# Flash.net
KiCad netlist of a schematic drawn in Altium Designer
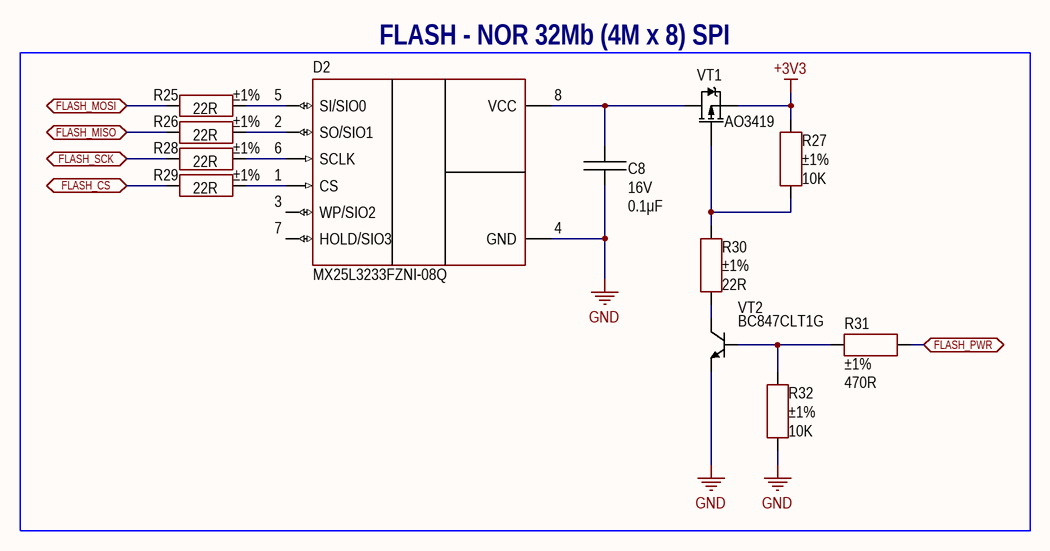
[diagram p0: Flash.SchDoc]

(export (version "E")
  (design (tool "Eeschema 10.0.6"))
  (components
    (comp (ref "C8")
      (value "0.1μF")
      (footprint "CAP: 0402")
      (description "±10% 16V Ceramic Capacitor X7R 0402 (1005 Metric)")
      (fields
        (field (name "MANUFACTURER") "Yageo")
        (field (name "PARTNUMBER") "CC0402KRX7R7BB104")
        (field (name "VOLTAGE") "16V")
      )
      (libsource (lib "capacitor") (part "Ceramic_0402"))
    )
    (comp (ref "D2")
      (value "~")
      (footprint "8-SOIC")
      (description "FLASH - NOR Memory IC 32Mb (8M x 4) SPI - Quad I/O 133 MHz 8-SOP")
      (fields
        (field (name "MANUFACTURER") "Macronix")
        (field (name "VALUEMANUFACTURERPARTNUMBER") "IC memory, FLASH, 32Mb (8M x 4), 133 MHz, SPI/QuadSPI, 2.7...3.6V, -40...+85°C, 8-SOIC")
        (field (name "PARTNUMBER") "MX25L3233FZNI-08Q")
      )
      (libsource (lib "MyLib") (part "MX25L3233"))
    )
    (comp (ref "R25")
      (value "22R")
      (footprint "RES: 0402")
      (description "22 Ohms ±1% 0.063W, 1/16W Chip Resistor 0402 (1005 Metric) Moisture Resistant Thick Film")
      (fields
        (field (name "MANUFACTURER") "Yageo")
        (field (name "PARTNUMBER") "RC0402FR-0722RL")
        (field (name "TOLERANCE") "±1%")
      )
      (libsource (lib "resistor") (part "Resistor_0402"))
    )
    (comp (ref "R26")
      (value "22R")
      (footprint "RES: 0402")
      (description "22 Ohms ±1% 0.063W, 1/16W Chip Resistor 0402 (1005 Metric) Moisture Resistant Thick Film")
      (fields
        (field (name "MANUFACTURER") "Yageo")
        (field (name "PARTNUMBER") "RC0402FR-0722RL")
        (field (name "TOLERANCE") "±1%")
      )
      (libsource (lib "resistor") (part "Resistor_0402"))
    )
    (comp (ref "R27")
      (value "10K")
      (footprint "RES: 0402")
      (description "10 kOhms ±1% 0.063W, 1/16W Chip Resistor 0402 (1005 Metric) Moisture Resistant Thick Film")
      (fields
        (field (name "MANUFACTURER") "Yageo")
        (field (name "PARTNUMBER") "RC0402FR-0710KL")
        (field (name "TOLERANCE") "±1%")
      )
      (libsource (lib "resistor") (part "Resistor_0402"))
    )
    (comp (ref "R28")
      (value "22R")
      (footprint "RES: 0402")
      (description "22 Ohms ±1% 0.063W, 1/16W Chip Resistor 0402 (1005 Metric) Moisture Resistant Thick Film")
      (fields
        (field (name "MANUFACTURER") "Yageo")
        (field (name "PARTNUMBER") "RC0402FR-0722RL")
        (field (name "TOLERANCE") "±1%")
      )
      (libsource (lib "resistor") (part "Resistor_0402"))
    )
    (comp (ref "R29")
      (value "22R")
      (footprint "RES: 0402")
      (description "22 Ohms ±1% 0.063W, 1/16W Chip Resistor 0402 (1005 Metric) Moisture Resistant Thick Film")
      (fields
        (field (name "MANUFACTURER") "Yageo")
        (field (name "PARTNUMBER") "RC0402FR-0722RL")
        (field (name "TOLERANCE") "±1%")
      )
      (libsource (lib "resistor") (part "Resistor_0402"))
    )
    (comp (ref "R30")
      (value "22R")
      (footprint "RES: 0402")
      (description "22 Ohms ±1% 0.063W, 1/16W Chip Resistor 0402 (1005 Metric) Moisture Resistant Thick Film")
      (fields
        (field (name "MANUFACTURER") "Yageo")
        (field (name "PARTNUMBER") "RC0402FR-0722RL")
        (field (name "TOLERANCE") "±1%")
      )
      (libsource (lib "") (part "Resistor_0402_1"))
    )
    (comp (ref "R31")
      (value "470R")
      (footprint "RES: 0402")
      (description "470 Ohms ±1% 0.063W, 1/16W Chip Resistor 0402 (1005 Metric) Moisture Resistant Thick Film")
      (fields
        (field (name "MANUFACTURER") "Yageo")
        (field (name "PARTNUMBER") "RC0402FR-07470RL")
        (field (name "TOLERANCE") "±1%")
      )
      (libsource (lib "resistor") (part "Resistor_0402"))
    )
    (comp (ref "R32")
      (value "10K")
      (footprint "RES: 0402")
      (description "10 kOhms ±1% 0.063W, 1/16W Chip Resistor 0402 (1005 Metric) Moisture Resistant Thick Film")
      (fields
        (field (name "MANUFACTURER") "Yageo")
        (field (name "PARTNUMBER") "RC0402FR-0710KL")
        (field (name "TOLERANCE") "±1%")
      )
      (libsource (lib "resistor") (part "Resistor_0402"))
    )
    (comp (ref "VT1")
      (value "~")
      (footprint "SOT23")
      (description "P-Channel 20 V 3.5A (Ta) 1.4W (Ta) Surface Mount SOT-23-3")
      (fields
        (field (name "MANUFACTURER") "Alpha & Omega Semiconductor")
        (field (name "VALUEMANUFACTURERPARTNUMBER") "MOSFET P-channel transistor, 20V, 3.5A, 4.4nC, 2.5W, 85mOhm, 400pF, SOT-23-3, -55...+150°C")
        (field (name "PARTNUMBER") "AO3419")
      )
      (libsource (lib "transistor") (part "MOSFET_P_132"))
    )
    (comp (ref "VT2")
      (value "~")
      (footprint "SOT23")
      (description "Bipolar (BJT) Transistor NPN 45 V 100 mA 100MHz 300 mW Surface Mount SOT-23-3 (TO-236)")
      (fields
        (field (name "MANUFACTURER") "ON Semiconductor")
        (field (name "VALUEMANUFACTURERPARTNUMBER") "NPN transistor, 45V, 100mA, 100MHz, 300mW, 0.6V, 420, SOT-23, -55...+125°C")
        (field (name "PARTNUMBER") "BC847CLT1G")
      )
      (libsource (lib "transistor") (part "BJT_NPN_132"))
    )
  )
  (nets
    (net (code "1") (name "+3V3") (class "Default")
      (node (ref "R27") (pin "2") (pinfunction "2_2") (pintype "passive"))
      (node (ref "VT1") (pin "2") (pinfunction "S_2") (pintype "passive"))
    )
    (net (code "2") (name "/FLASH_CS") (class "Default")
      (node (ref "R29") (pin "1") (pinfunction "1_1") (pintype "passive"))
    )
    (net (code "3") (name "/FLASH_MISO") (class "Default")
      (node (ref "R26") (pin "1") (pinfunction "1_1") (pintype "passive"))
    )
    (net (code "4") (name "/FLASH_MOSI") (class "Default")
      (node (ref "R25") (pin "1") (pinfunction "1_1") (pintype "passive"))
    )
    (net (code "5") (name "/FLASH_PWR") (class "Default")
      (node (ref "R31") (pin "2") (pinfunction "2_2") (pintype "passive"))
    )
    (net (code "6") (name "/FLASH_SCK") (class "Default")
      (node (ref "R28") (pin "1") (pinfunction "1_1") (pintype "passive"))
    )
    (net (code "7") (name "GND") (class "Default")
      (node (ref "C8") (pin "1") (pinfunction "1_1") (pintype "passive"))
      (node (ref "D2") (pin "4") (pinfunction "GND_4") (pintype "power_in"))
      (node (ref "R32") (pin "1") (pinfunction "1_1") (pintype "passive"))
      (node (ref "VT2") (pin "2") (pinfunction "E_2") (pintype "passive"))
    )
    (net (code "8") (name "Net-(D2-CS)") (class "Default")
      (node (ref "D2") (pin "1") (pinfunction "CS_1") (pintype "input"))
      (node (ref "R29") (pin "2") (pinfunction "2_2") (pintype "passive"))
    )
    (net (code "9") (name "Net-(D2-SCLK)") (class "Default")
      (node (ref "D2") (pin "6") (pinfunction "SCLK_6") (pintype "input"))
      (node (ref "R28") (pin "2") (pinfunction "2_2") (pintype "passive"))
    )
    (net (code "10") (name "Net-(D2-SI{slash}SIO0)") (class "Default")
      (node (ref "D2") (pin "5") (pinfunction "SI/SIO0_5") (pintype "bidirectional"))
      (node (ref "R25") (pin "2") (pinfunction "2_2") (pintype "passive"))
    )
    (net (code "11") (name "Net-(D2-SO{slash}SIO1)") (class "Default")
      (node (ref "D2") (pin "2") (pinfunction "SO/SIO1_2") (pintype "bidirectional"))
      (node (ref "R26") (pin "2") (pinfunction "2_2") (pintype "passive"))
    )
    (net (code "12") (name "Net-(D2-VCC)") (class "Default")
      (node (ref "C8") (pin "2") (pinfunction "2_2") (pintype "passive"))
      (node (ref "D2") (pin "8") (pinfunction "VCC_8") (pintype "power_in"))
      (node (ref "VT1") (pin "3") (pinfunction "D_3") (pintype "passive"))
    )
    (net (code "13") (name "Net-(VT1-G)") (class "Default")
      (node (ref "R27") (pin "1") (pinfunction "1_1") (pintype "passive"))
      (node (ref "R30") (pin "2") (pinfunction "2_2") (pintype "passive"))
      (node (ref "VT1") (pin "1") (pinfunction "G_1") (pintype "passive"))
    )
    (net (code "14") (name "Net-(VT2-B)") (class "Default")
      (node (ref "R31") (pin "1") (pinfunction "1_1") (pintype "passive"))
      (node (ref "R32") (pin "2") (pinfunction "2_2") (pintype "passive"))
      (node (ref "VT2") (pin "1") (pinfunction "B_1") (pintype "passive"))
    )
    (net (code "15") (name "Net-(VT2-C)") (class "Default")
      (node (ref "R30") (pin "1") (pinfunction "1_1") (pintype "passive"))
      (node (ref "VT2") (pin "3") (pinfunction "C_3") (pintype "passive"))
    )
    (net (code "16") (name "unconnected-(D2-HOLD{slash}SIO3-Pad7)") (class "Default")
      (node (ref "D2") (pin "7") (pinfunction "HOLD/SIO3_7") (pintype "bidirectional"))
    )
    (net (code "17") (name "unconnected-(D2-WP{slash}SIO2-Pad3)") (class "Default")
      (node (ref "D2") (pin "3") (pinfunction "WP/SIO2_3") (pintype "bidirectional"))
    )
  )
)
